# ATTINY85flasher.net
KiCad netlist of a schematic drawn in EAGLE
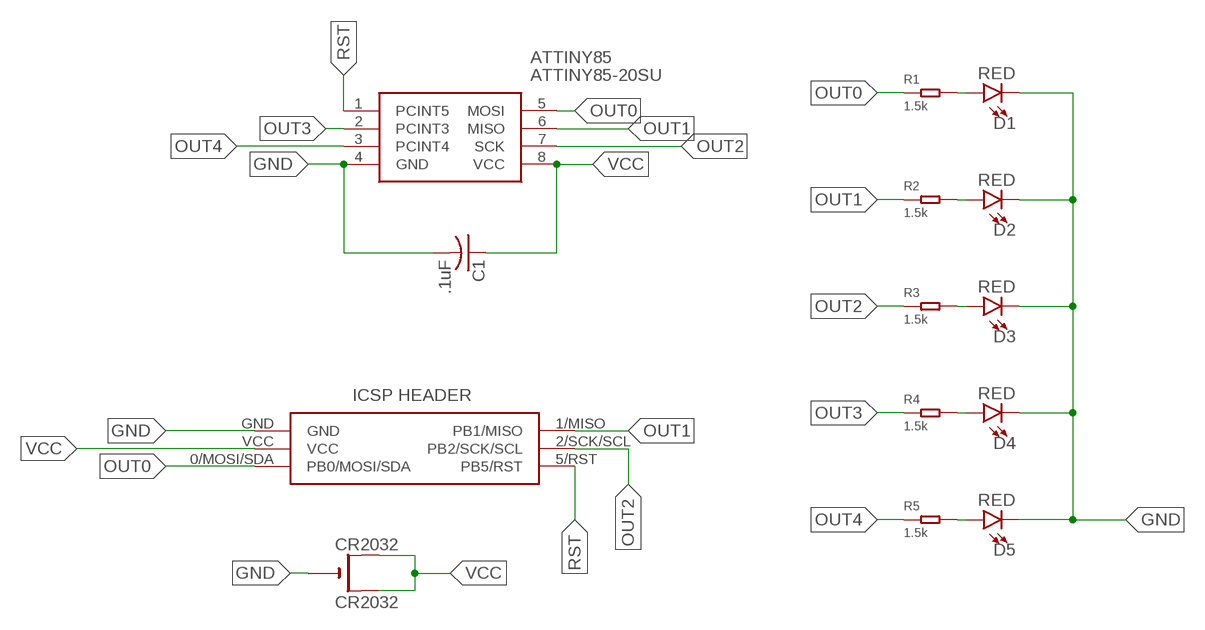
[diagram p0: schematic, sheet 1]

(export (version "E")
  (design (tool "Eeschema 10.0.6"))
  (components
    (comp (ref "ATTINY85")
      (value "ATTINY85-20SU")
      (footprint "eagle-import:SOT127P798X216-8N")
      (fields (field (name "RS_PART_NUMBER") "1331674"))
      (libsource (lib "eagle-import") (part "ATTINY85-20SU"))
    )
    (comp (ref "C1")
      (value ".1uF")
      (footprint "eagle-import:C0603")
      (libsource (lib "eagle-import") (part "C-USC0603"))
    )
    (comp (ref "CR2032")
      (value "CR2032")
      (footprint "eagle-import:CR2032-SMD")
      (libsource (lib "eagle-import") (part "CR2032SMT"))
    )
    (comp (ref "D1")
      (value "RED")
      (footprint "eagle-import:LED-1206")
      (libsource (lib "eagle-import") (part "LED-RED1206"))
    )
    (comp (ref "D2")
      (value "RED")
      (footprint "eagle-import:LED-1206")
      (libsource (lib "eagle-import") (part "LED-RED1206"))
    )
    (comp (ref "D3")
      (value "RED")
      (footprint "eagle-import:LED-1206")
      (libsource (lib "eagle-import") (part "LED-RED1206"))
    )
    (comp (ref "D4")
      (value "RED")
      (footprint "eagle-import:LED-1206")
      (libsource (lib "eagle-import") (part "LED-RED1206"))
    )
    (comp (ref "D5")
      (value "RED")
      (footprint "eagle-import:LED-1206")
      (libsource (lib "eagle-import") (part "LED-RED1206"))
    )
    (comp (ref "J1")
      (value "ICSP-LO-SILK")
      (footprint "eagle-import:ICSP-LO-SILK")
      (libsource (lib "eagle-import") (part "ICSP-LO-SILK"))
    )
    (comp (ref "R1")
      (value "1.5k")
      (footprint "eagle-import:R1206")
      (fields (field (name "MPN") "RC1206JR-0713RL"))
      (libsource (lib "eagle-import") (part "SMD-RES-13R-5%-1/4W(1206)"))
    )
    (comp (ref "R2")
      (value "1.5k")
      (footprint "eagle-import:R1206")
      (fields (field (name "MPN") "RC1206JR-0713RL"))
      (libsource (lib "eagle-import") (part "SMD-RES-13R-5%-1/4W(1206)"))
    )
    (comp (ref "R3")
      (value "1.5k")
      (footprint "eagle-import:R1206")
      (fields (field (name "MPN") "RC1206JR-0713RL"))
      (libsource (lib "eagle-import") (part "SMD-RES-13R-5%-1/4W(1206)"))
    )
    (comp (ref "R4")
      (value "1.5k")
      (footprint "eagle-import:R1206")
      (fields (field (name "MPN") "RC1206JR-0713RL"))
      (libsource (lib "eagle-import") (part "SMD-RES-13R-5%-1/4W(1206)"))
    )
    (comp (ref "R5")
      (value "1.5k")
      (footprint "eagle-import:R1206")
      (fields (field (name "MPN") "RC1206JR-0713RL"))
      (libsource (lib "eagle-import") (part "SMD-RES-13R-5%-1/4W(1206)"))
    )
  )
  (nets
    (net (code "1") (name "GND") (class "Default")
      (node (ref "ATTINY85") (pin "4") (pinfunction "GND_4") (pintype "power_in"))
      (node (ref "C1") (pin "2") (pinfunction "2_2") (pintype "passive"))
      (node (ref "CR2032") (pin "-") (pinfunction "-_-") (pintype "passive"))
      (node (ref "D1") (pin "C") (pinfunction "C_C") (pintype "passive"))
      (node (ref "D2") (pin "C") (pinfunction "C_C") (pintype "passive"))
      (node (ref "D3") (pin "C") (pinfunction "C_C") (pintype "passive"))
      (node (ref "D4") (pin "C") (pinfunction "C_C") (pintype "passive"))
      (node (ref "D5") (pin "C") (pinfunction "C_C") (pintype "passive"))
      (node (ref "J1") (pin "GND") (pinfunction "GND_GND") (pintype "bidirectional"))
    )
    (net (code "2") (name "Net-(D1-PadA)") (class "Default")
      (node (ref "D1") (pin "A") (pinfunction "A_A") (pintype "passive"))
      (node (ref "R1") (pin "2") (pinfunction "2_2") (pintype "passive"))
    )
    (net (code "3") (name "Net-(D2-PadA)") (class "Default")
      (node (ref "D2") (pin "A") (pinfunction "A_A") (pintype "passive"))
      (node (ref "R2") (pin "2") (pinfunction "2_2") (pintype "passive"))
    )
    (net (code "4") (name "Net-(D3-PadA)") (class "Default")
      (node (ref "D3") (pin "A") (pinfunction "A_A") (pintype "passive"))
      (node (ref "R3") (pin "2") (pinfunction "2_2") (pintype "passive"))
    )
    (net (code "5") (name "Net-(D4-PadA)") (class "Default")
      (node (ref "D4") (pin "A") (pinfunction "A_A") (pintype "passive"))
      (node (ref "R4") (pin "2") (pinfunction "2_2") (pintype "passive"))
    )
    (net (code "6") (name "Net-(D5-PadA)") (class "Default")
      (node (ref "D5") (pin "A") (pinfunction "A_A") (pintype "passive"))
      (node (ref "R5") (pin "2") (pinfunction "2_2") (pintype "passive"))
    )
    (net (code "7") (name "OUT0") (class "Default")
      (node (ref "ATTINY85") (pin "5") (pinfunction "MOSI_5") (pintype "bidirectional"))
      (node (ref "J1") (pin "0/MOSI/SDA") (pinfunction "PB0/MOSI/SDA_0/MOSI/SDA") (pintype "bidirectional"))
      (node (ref "R1") (pin "1") (pinfunction "1_1") (pintype "passive"))
    )
    (net (code "8") (name "OUT1") (class "Default")
      (node (ref "ATTINY85") (pin "6") (pinfunction "MISO_6") (pintype "bidirectional"))
      (node (ref "J1") (pin "1/MISO") (pinfunction "PB1/MISO_1/MISO") (pintype "bidirectional"))
      (node (ref "R2") (pin "1") (pinfunction "1_1") (pintype "passive"))
    )
    (net (code "9") (name "OUT2") (class "Default")
      (node (ref "ATTINY85") (pin "7") (pinfunction "SCK_7") (pintype "bidirectional"))
      (node (ref "J1") (pin "2/SCK/SCL") (pinfunction "PB2/SCK/SCL_2/SCK/SCL") (pintype "bidirectional"))
      (node (ref "R3") (pin "1") (pinfunction "1_1") (pintype "passive"))
    )
    (net (code "10") (name "OUT3") (class "Default")
      (node (ref "ATTINY85") (pin "2") (pinfunction "PCINT3_2") (pintype "bidirectional"))
      (node (ref "R4") (pin "1") (pinfunction "1_1") (pintype "passive"))
    )
    (net (code "11") (name "OUT4") (class "Default")
      (node (ref "ATTINY85") (pin "3") (pinfunction "PCINT4_3") (pintype "bidirectional"))
      (node (ref "R5") (pin "1") (pinfunction "1_1") (pintype "passive"))
    )
    (net (code "12") (name "RST") (class "Default")
      (node (ref "ATTINY85") (pin "1") (pinfunction "PCINT5_1") (pintype "bidirectional"))
      (node (ref "J1") (pin "5/RST") (pinfunction "PB5/RST_5/RST") (pintype "bidirectional"))
    )
    (net (code "13") (name "VCC") (class "Default")
      (node (ref "ATTINY85") (pin "8") (pinfunction "VCC_8") (pintype "power_in"))
      (node (ref "C1") (pin "1") (pinfunction "1_1") (pintype "passive"))
      (node (ref "CR2032") (pin "+$1") (pinfunction "+_+$1") (pintype "passive"))
      (node (ref "CR2032") (pin "+$2") (pinfunction "+1_+$2") (pintype "passive"))
      (node (ref "J1") (pin "VCC") (pinfunction "VCC_VCC") (pintype "bidirectional"))
    )
  )
)
